# SB-FLOOR-LIGHTS.net
KiCad netlist of a schematic drawn in EAGLE
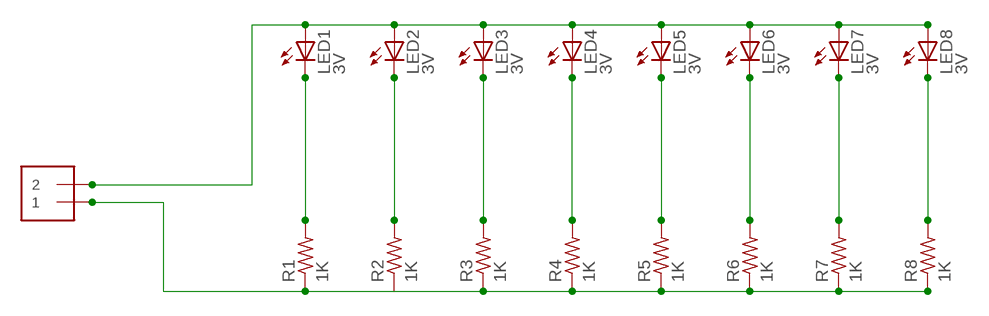
[diagram p0: schematic, sheet 1]

(export (version "E")
  (design (tool "Eeschema 10.0.6"))
  (components
    (comp (ref "J1")
      (value "1X2-3.5MM")
      (footprint "eagle-import:1X2-3.5MM")
      (libsource (lib "eagle-import") (part "1X2-3.5MM"))
    )
    (comp (ref "LED1")
      (value "3V")
      (footprint "eagle-import:CHIPLED_0603")
      (libsource (lib "eagle-import") (part "LEDCHIPLED_0603"))
    )
    (comp (ref "LED2")
      (value "3V")
      (footprint "eagle-import:CHIPLED_0603")
      (libsource (lib "eagle-import") (part "LEDCHIPLED_0603"))
    )
    (comp (ref "LED3")
      (value "3V")
      (footprint "eagle-import:CHIPLED_0603")
      (libsource (lib "eagle-import") (part "LEDCHIPLED_0603"))
    )
    (comp (ref "LED4")
      (value "3V")
      (footprint "eagle-import:CHIPLED_0603")
      (libsource (lib "eagle-import") (part "LEDCHIPLED_0603"))
    )
    (comp (ref "LED5")
      (value "3V")
      (footprint "eagle-import:CHIPLED_0603")
      (libsource (lib "eagle-import") (part "LEDCHIPLED_0603"))
    )
    (comp (ref "LED6")
      (value "3V")
      (footprint "eagle-import:CHIPLED_0603")
      (libsource (lib "eagle-import") (part "LEDCHIPLED_0603"))
    )
    (comp (ref "LED7")
      (value "3V")
      (footprint "eagle-import:CHIPLED_0603")
      (libsource (lib "eagle-import") (part "LEDCHIPLED_0603"))
    )
    (comp (ref "LED8")
      (value "3V")
      (footprint "eagle-import:CHIPLED_0603")
      (libsource (lib "eagle-import") (part "LEDCHIPLED_0603"))
    )
    (comp (ref "R1")
      (value "1K")
      (footprint "eagle-import:R0603")
      (libsource (lib "eagle-import") (part "R-US_R0603"))
    )
    (comp (ref "R2")
      (value "1K")
      (footprint "eagle-import:R0603")
      (libsource (lib "eagle-import") (part "R-US_R0603"))
    )
    (comp (ref "R3")
      (value "1K")
      (footprint "eagle-import:R0603")
      (libsource (lib "eagle-import") (part "R-US_R0603"))
    )
    (comp (ref "R4")
      (value "1K")
      (footprint "eagle-import:R0603")
      (libsource (lib "eagle-import") (part "R-US_R0603"))
    )
    (comp (ref "R5")
      (value "1K")
      (footprint "eagle-import:R0603")
      (libsource (lib "eagle-import") (part "R-US_R0603"))
    )
    (comp (ref "R6")
      (value "1K")
      (footprint "eagle-import:R0603")
      (libsource (lib "eagle-import") (part "R-US_R0603"))
    )
    (comp (ref "R7")
      (value "1K")
      (footprint "eagle-import:R0603")
      (libsource (lib "eagle-import") (part "R-US_R0603"))
    )
    (comp (ref "R8")
      (value "1K")
      (footprint "eagle-import:R0603")
      (libsource (lib "eagle-import") (part "R-US_R0603"))
    )
  )
  (nets
    (net (code "1") (name "Net-(J1-Pad1)") (class "Default")
      (node (ref "J1") (pin "1") (pinfunction "1_1") (pintype "passive"))
      (node (ref "R1") (pin "1") (pinfunction "1_1") (pintype "passive"))
      (node (ref "R2") (pin "1") (pinfunction "1_1") (pintype "passive"))
      (node (ref "R3") (pin "1") (pinfunction "1_1") (pintype "passive"))
      (node (ref "R4") (pin "1") (pinfunction "1_1") (pintype "passive"))
      (node (ref "R5") (pin "1") (pinfunction "1_1") (pintype "passive"))
      (node (ref "R6") (pin "1") (pinfunction "1_1") (pintype "passive"))
      (node (ref "R7") (pin "1") (pinfunction "1_1") (pintype "passive"))
      (node (ref "R8") (pin "1") (pinfunction "1_1") (pintype "passive"))
    )
    (net (code "2") (name "Net-(J1-Pad2)") (class "Default")
      (node (ref "J1") (pin "2") (pinfunction "2_2") (pintype "passive"))
      (node (ref "LED1") (pin "A") (pinfunction "A_A") (pintype "passive"))
      (node (ref "LED2") (pin "A") (pinfunction "A_A") (pintype "passive"))
      (node (ref "LED3") (pin "A") (pinfunction "A_A") (pintype "passive"))
      (node (ref "LED4") (pin "A") (pinfunction "A_A") (pintype "passive"))
      (node (ref "LED5") (pin "A") (pinfunction "A_A") (pintype "passive"))
      (node (ref "LED6") (pin "A") (pinfunction "A_A") (pintype "passive"))
      (node (ref "LED7") (pin "A") (pinfunction "A_A") (pintype "passive"))
      (node (ref "LED8") (pin "A") (pinfunction "A_A") (pintype "passive"))
    )
    (net (code "3") (name "Net-(LED1-PadC)") (class "Default")
      (node (ref "LED1") (pin "C") (pinfunction "C_C") (pintype "passive"))
      (node (ref "R1") (pin "2") (pinfunction "2_2") (pintype "passive"))
    )
    (net (code "4") (name "Net-(LED2-PadC)") (class "Default")
      (node (ref "LED2") (pin "C") (pinfunction "C_C") (pintype "passive"))
      (node (ref "R2") (pin "2") (pinfunction "2_2") (pintype "passive"))
    )
    (net (code "5") (name "Net-(LED3-PadC)") (class "Default")
      (node (ref "LED3") (pin "C") (pinfunction "C_C") (pintype "passive"))
      (node (ref "R3") (pin "2") (pinfunction "2_2") (pintype "passive"))
    )
    (net (code "6") (name "Net-(LED4-PadC)") (class "Default")
      (node (ref "LED4") (pin "C") (pinfunction "C_C") (pintype "passive"))
      (node (ref "R4") (pin "2") (pinfunction "2_2") (pintype "passive"))
    )
    (net (code "7") (name "Net-(LED5-PadC)") (class "Default")
      (node (ref "LED5") (pin "C") (pinfunction "C_C") (pintype "passive"))
      (node (ref "R5") (pin "2") (pinfunction "2_2") (pintype "passive"))
    )
    (net (code "8") (name "Net-(LED6-PadC)") (class "Default")
      (node (ref "LED6") (pin "C") (pinfunction "C_C") (pintype "passive"))
      (node (ref "R6") (pin "2") (pinfunction "2_2") (pintype "passive"))
    )
    (net (code "9") (name "Net-(LED7-PadC)") (class "Default")
      (node (ref "LED7") (pin "C") (pinfunction "C_C") (pintype "passive"))
      (node (ref "R7") (pin "2") (pinfunction "2_2") (pintype "passive"))
    )
    (net (code "10") (name "Net-(LED8-PadC)") (class "Default")
      (node (ref "LED8") (pin "C") (pinfunction "C_C") (pintype "passive"))
      (node (ref "R8") (pin "2") (pinfunction "2_2") (pintype "passive"))
    )
  )
)
